# module_SX1278_type1.net
KiCad netlist of a schematic drawn in EAGLE
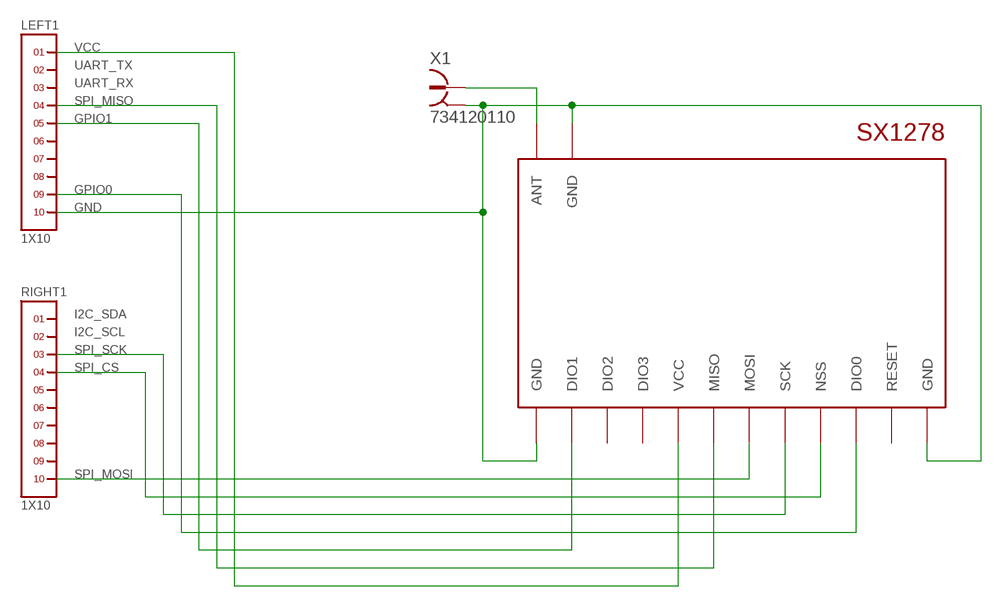
[diagram p0: schematic, sheet 1]

(export (version "E")
  (design (tool "Eeschema 10.0.6"))
  (components
    (comp (ref "LEFT1")
      (value "1X10")
      (footprint "eagle-import:1X10")
      (libsource (lib "eagle-import") (part "1X10"))
    )
    (comp (ref "RIGHT1")
      (value "1X10")
      (footprint "eagle-import:1X10")
      (libsource (lib "eagle-import") (part "1X10"))
    )
    (comp (ref "U$1")
      (value "SX1278_1")
      (footprint "eagle-import:SX1278_1")
      (libsource (lib "eagle-import") (part "SX1278_1"))
    )
    (comp (ref "X1")
      (value "734120110")
      (footprint "eagle-import:734120110")
      (libsource (lib "eagle-import") (part "734120110"))
    )
  )
  (nets
    (net (code "1") (name "Net-(LEFT1-Pad1)") (class "Default")
      (node (ref "LEFT1") (pin "1") (pinfunction "1_1") (pintype "bidirectional"))
      (node (ref "U$1") (pin "VCC") (pinfunction "VCC_VCC") (pintype "bidirectional"))
    )
    (net (code "2") (name "Net-(LEFT1-Pad4)") (class "Default")
      (node (ref "LEFT1") (pin "4") (pinfunction "4_4") (pintype "bidirectional"))
      (node (ref "U$1") (pin "MISO") (pinfunction "MISO_MISO") (pintype "bidirectional"))
    )
    (net (code "3") (name "Net-(LEFT1-Pad5)") (class "Default")
      (node (ref "LEFT1") (pin "5") (pinfunction "5_5") (pintype "bidirectional"))
      (node (ref "U$1") (pin "DIO1") (pinfunction "DIO1_DIO1") (pintype "bidirectional"))
    )
    (net (code "4") (name "Net-(LEFT1-Pad9)") (class "Default")
      (node (ref "LEFT1") (pin "9") (pinfunction "9_9") (pintype "bidirectional"))
      (node (ref "U$1") (pin "DIO0") (pinfunction "DIO0_DIO0") (pintype "bidirectional"))
    )
    (net (code "5") (name "Net-(LEFT1-Pad10)") (class "Default")
      (node (ref "LEFT1") (pin "10") (pinfunction "10_10") (pintype "bidirectional"))
      (node (ref "U$1") (pin "GND@1") (pinfunction "GND_GND@1") (pintype "bidirectional"))
      (node (ref "U$1") (pin "GND@2") (pinfunction "GND_GND@2") (pintype "bidirectional"))
      (node (ref "U$1") (pin "GND@3") (pinfunction "GND_GND@3") (pintype "bidirectional"))
      (node (ref "X1") (pin "S@1") (pinfunction "2_S@1") (pintype "passive"))
      (node (ref "X1") (pin "S@2") (pinfunction "2_S@2") (pintype "passive"))
      (node (ref "X1") (pin "S@3") (pinfunction "2_S@3") (pintype "passive"))
    )
    (net (code "6") (name "Net-(RIGHT1-Pad3)") (class "Default")
      (node (ref "RIGHT1") (pin "3") (pinfunction "3_3") (pintype "bidirectional"))
      (node (ref "U$1") (pin "SCK") (pinfunction "SCK_SCK") (pintype "bidirectional"))
    )
    (net (code "7") (name "Net-(RIGHT1-Pad4)") (class "Default")
      (node (ref "RIGHT1") (pin "4") (pinfunction "4_4") (pintype "bidirectional"))
      (node (ref "U$1") (pin "NSS") (pinfunction "NSS_NSS") (pintype "bidirectional"))
    )
    (net (code "8") (name "Net-(RIGHT1-Pad10)") (class "Default")
      (node (ref "RIGHT1") (pin "10") (pinfunction "10_10") (pintype "bidirectional"))
      (node (ref "U$1") (pin "MOSI") (pinfunction "MOSI_MOSI") (pintype "bidirectional"))
    )
    (net (code "9") (name "Net-(U$1-PadANT)") (class "Default")
      (node (ref "U$1") (pin "ANT") (pinfunction "ANT_ANT") (pintype "bidirectional"))
      (node (ref "X1") (pin "1") (pinfunction "1_1") (pintype "passive"))
    )
    (net (code "10") (name "unconnected-(LEFT1-Pad2)") (class "Default")
      (node (ref "LEFT1") (pin "2") (pinfunction "2_2") (pintype "bidirectional"))
    )
    (net (code "11") (name "unconnected-(LEFT1-Pad3)") (class "Default")
      (node (ref "LEFT1") (pin "3") (pinfunction "3_3") (pintype "bidirectional"))
    )
    (net (code "12") (name "unconnected-(LEFT1-Pad6)") (class "Default")
      (node (ref "LEFT1") (pin "6") (pinfunction "6_6") (pintype "bidirectional"))
    )
    (net (code "13") (name "unconnected-(LEFT1-Pad7)") (class "Default")
      (node (ref "LEFT1") (pin "7") (pinfunction "7_7") (pintype "bidirectional"))
    )
    (net (code "14") (name "unconnected-(LEFT1-Pad8)") (class "Default")
      (node (ref "LEFT1") (pin "8") (pinfunction "8_8") (pintype "bidirectional"))
    )
    (net (code "15") (name "unconnected-(RIGHT1-Pad1)") (class "Default")
      (node (ref "RIGHT1") (pin "1") (pinfunction "1_1") (pintype "bidirectional"))
    )
    (net (code "16") (name "unconnected-(RIGHT1-Pad2)") (class "Default")
      (node (ref "RIGHT1") (pin "2") (pinfunction "2_2") (pintype "bidirectional"))
    )
    (net (code "17") (name "unconnected-(RIGHT1-Pad5)") (class "Default")
      (node (ref "RIGHT1") (pin "5") (pinfunction "5_5") (pintype "bidirectional"))
    )
    (net (code "18") (name "unconnected-(RIGHT1-Pad6)") (class "Default")
      (node (ref "RIGHT1") (pin "6") (pinfunction "6_6") (pintype "bidirectional"))
    )
    (net (code "19") (name "unconnected-(RIGHT1-Pad7)") (class "Default")
      (node (ref "RIGHT1") (pin "7") (pinfunction "7_7") (pintype "bidirectional"))
    )
    (net (code "20") (name "unconnected-(RIGHT1-Pad8)") (class "Default")
      (node (ref "RIGHT1") (pin "8") (pinfunction "8_8") (pintype "bidirectional"))
    )
    (net (code "21") (name "unconnected-(RIGHT1-Pad9)") (class "Default")
      (node (ref "RIGHT1") (pin "9") (pinfunction "9_9") (pintype "bidirectional"))
    )
    (net (code "22") (name "unconnected-(U$1-PadDIO2)") (class "Default")
      (node (ref "U$1") (pin "DIO2") (pinfunction "DIO2_DIO2") (pintype "bidirectional"))
    )
    (net (code "23") (name "unconnected-(U$1-PadDIO3)") (class "Default")
      (node (ref "U$1") (pin "DIO3") (pinfunction "DIO3_DIO3") (pintype "bidirectional"))
    )
    (net (code "24") (name "unconnected-(U$1-PadRESET)") (class "Default")
      (node (ref "U$1") (pin "RESET") (pinfunction "RESET_RESET") (pintype "bidirectional"))
    )
  )
)
